# dcdc.net
KiCad netlist of a schematic drawn in Altium Designer
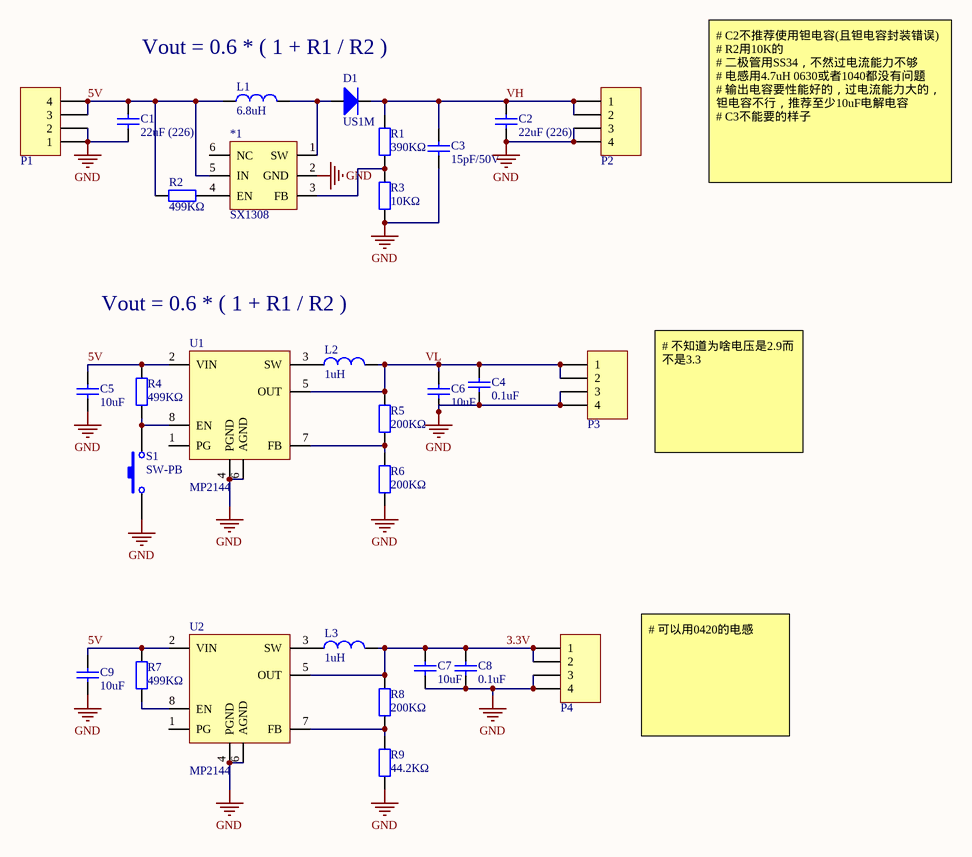
[diagram p0: dcdc.SchDoc]

(export (version "E")
  (design (tool "Eeschema 10.0.6"))
  (components
    (comp (ref "*1")
      (value "SX1308")
      (footprint "SOT23-6")
      (description "小体积高效升压电路最高28V")
      (libsource (lib "fszhang") (part "SX1308"))
    )
    (comp (ref "C1")
      (value "22uF (226)")
      (footprint "0805_C")
      (description "贴片电容")
      (libsource (lib "Miscellaneous Devices LC") (part "0805 22uF (226) 20% 25V"))
    )
    (comp (ref "C2")
      (value "22uF (226)")
      (footprint "CAP-7343")
      (description "贴片电容")
      (libsource (lib "Miscellaneous Devices LC") (part "0805 22uF (226) 20% 25V"))
    )
    (comp (ref "C3")
      (value "15pF/50V")
      (footprint "0805_C")
      (description "贴片电容")
      (libsource (lib "Miscellaneous Devices LC") (part "0805 22uF (226) 20% 25V"))
    )
    (comp (ref "C4")
      (value "0.1uF")
      (footprint "0805_C")
      (description "贴片电容")
      (libsource (lib "Miscellaneous Devices LC") (part "0805 10uF (106) 10% 25V"))
    )
    (comp (ref "C5")
      (value "10uF")
      (footprint "0805_C")
      (description "贴片电容")
      (libsource (lib "Miscellaneous Devices LC") (part "0805 10uF (106) 10% 25V"))
    )
    (comp (ref "C6")
      (value "10uF")
      (footprint "0805_C")
      (description "贴片电容")
      (libsource (lib "Miscellaneous Devices LC") (part "0805 10uF (106) 10% 25V"))
    )
    (comp (ref "C7")
      (value "10uF")
      (footprint "0805_C")
      (description "贴片电容")
      (libsource (lib "Miscellaneous Devices LC") (part "0805 10uF (106) 10% 25V"))
    )
    (comp (ref "C8")
      (value "0.1uF")
      (footprint "0805_C")
      (description "贴片电容")
      (libsource (lib "Miscellaneous Devices LC") (part "0805 10uF (106) 10% 25V"))
    )
    (comp (ref "C9")
      (value "10uF")
      (footprint "0805_C")
      (description "贴片电容")
      (libsource (lib "Miscellaneous Devices LC") (part "0805 10uF (106) 10% 25V"))
    )
    (comp (ref "D1")
      (value "US1M")
      (footprint "DIODE-SMA")
      (description "二极管")
      (fields (field (name "PUBLISHER") "Altium Limited"))
      (libsource (lib "fszhang") (part "Diode"))
    )
    (comp (ref "L1")
      (value "6.8uH")
      (footprint "CDRH104R")
      (description "电感")
      (fields (field (name "PUBLISHER") "Altium Limited"))
      (libsource (lib "fszhang") (part "Inductor"))
    )
    (comp (ref "L2")
      (value "1uH")
      (footprint "06030")
      (description "电感")
      (fields (field (name "PUBLISHER") "Altium Limited"))
      (libsource (lib "fszhang") (part "Inductor"))
    )
    (comp (ref "L3")
      (value "1uH")
      (footprint "06030")
      (description "电感")
      (fields (field (name "PUBLISHER") "Altium Limited"))
      (libsource (lib "fszhang") (part "Inductor"))
    )
    (comp (ref "P1")
      (value "Header 4")
      (footprint "HDR4X1_A")
      (description "接插件")
      (fields (field (name "PUBLISHER") "Altium Limited"))
      (libsource (lib "") (part "Header 4_1"))
    )
    (comp (ref "P2")
      (value "Header 4")
      (footprint "HDR4X1_A")
      (description "接插件")
      (fields (field (name "PUBLISHER") "Altium Limited"))
      (libsource (lib "fszhang") (part "Header 4"))
    )
    (comp (ref "P3")
      (value "Header 4")
      (footprint "HDR4X1_A")
      (description "接插件")
      (fields (field (name "PUBLISHER") "Altium Limited"))
      (libsource (lib "fszhang") (part "Header 4"))
    )
    (comp (ref "P4")
      (value "Header 4")
      (footprint "HDR4X1_A")
      (description "接插件")
      (fields (field (name "PUBLISHER") "Altium Limited"))
      (libsource (lib "fszhang") (part "Header 4"))
    )
    (comp (ref "R1")
      (value "390KΩ")
      (footprint "0805_R")
      (description "贴片电阻")
      (libsource (lib "Miscellaneous Devices LC") (part "0805 1.2KΩ (1201) 1%"))
    )
    (comp (ref "R2")
      (value "499KΩ")
      (footprint "0805_R")
      (description "贴片电阻")
      (libsource (lib "Miscellaneous Devices LC") (part "0805 100KΩ (1003) 1%"))
    )
    (comp (ref "R3")
      (value "10KΩ")
      (footprint "0805_R")
      (description "贴片电阻")
      (libsource (lib "Miscellaneous Devices LC") (part "0805 1.2KΩ (1201) 1%"))
    )
    (comp (ref "R4")
      (value "499KΩ")
      (footprint "0805_R")
      (description "贴片电阻")
      (libsource (lib "Miscellaneous Devices LC") (part "0805 200KΩ (2003) 1%"))
    )
    (comp (ref "R5")
      (value "200KΩ")
      (footprint "0805_R")
      (description "贴片电阻")
      (libsource (lib "") (part "0805 200KΩ (2003) 1%_1"))
    )
    (comp (ref "R6")
      (value "200KΩ")
      (footprint "0805_R")
      (description "贴片电阻")
      (libsource (lib "Miscellaneous Devices LC") (part "0805 200KΩ (2003) 1%"))
    )
    (comp (ref "R7")
      (value "499KΩ")
      (footprint "0805_R")
      (description "贴片电阻")
      (libsource (lib "Miscellaneous Devices LC") (part "0805 200KΩ (2003) 1%"))
    )
    (comp (ref "R8")
      (value "200KΩ")
      (footprint "0805_R")
      (description "贴片电阻")
      (libsource (lib "") (part "0805 200KΩ (2003) 1%_1"))
    )
    (comp (ref "R9")
      (value "44.2KΩ")
      (footprint "0805_R")
      (description "贴片电阻")
      (libsource (lib "Miscellaneous Devices LC") (part "0805 200KΩ (2003) 1%"))
    )
    (comp (ref "S1")
      (value "SW-PB")
      (footprint "SW_PB2_A2")
      (description "微动开关key")
      (fields (field (name "PUBLISHER") "Altium Limited"))
      (libsource (lib "fszhang") (part "SW-PB"))
    )
    (comp (ref "U1")
      (value "MP2144")
      (footprint "TSOT23-8")
      (description "小体积高效降压 有推荐pcb布局")
      (libsource (lib "fszhang") (part "MP2144"))
    )
    (comp (ref "U2")
      (value "MP2144")
      (footprint "TSOT23-8")
      (description "小体积高效降压 有推荐pcb布局")
      (libsource (lib "fszhang") (part "MP2144"))
    )
  )
  (nets
    (net (code "1") (name "/3.3V") (class "Default")
      (node (ref "C7") (pin "2") (pinfunction "2_2") (pintype "passive"))
      (node (ref "C8") (pin "2") (pinfunction "2_2") (pintype "passive"))
      (node (ref "L3") (pin "2") (pinfunction "2_2") (pintype "passive"))
      (node (ref "P4") (pin "1") (pinfunction "1_1") (pintype "passive"))
      (node (ref "P4") (pin "2") (pinfunction "2_2") (pintype "passive"))
      (node (ref "R8") (pin "1") (pinfunction "1_1") (pintype "passive"))
      (node (ref "U2") (pin "5") (pinfunction "OUT_5") (pintype "passive"))
    )
    (net (code "2") (name "/5V") (class "Default")
      (node (ref "*1") (pin "5") (pinfunction "IN_5") (pintype "passive"))
      (node (ref "C1") (pin "2") (pinfunction "2_2") (pintype "passive"))
      (node (ref "C5") (pin "2") (pinfunction "2_2") (pintype "passive"))
      (node (ref "C9") (pin "2") (pinfunction "2_2") (pintype "passive"))
      (node (ref "L1") (pin "1") (pinfunction "1_1") (pintype "passive"))
      (node (ref "P1") (pin "3") (pinfunction "3_3") (pintype "passive"))
      (node (ref "P1") (pin "4") (pinfunction "4_4") (pintype "passive"))
      (node (ref "R2") (pin "1") (pinfunction "1_1") (pintype "passive"))
      (node (ref "R4") (pin "2") (pinfunction "2_2") (pintype "passive"))
      (node (ref "R7") (pin "2") (pinfunction "2_2") (pintype "passive"))
      (node (ref "U1") (pin "2") (pinfunction "VIN_2") (pintype "passive"))
      (node (ref "U2") (pin "2") (pinfunction "VIN_2") (pintype "passive"))
    )
    (net (code "3") (name "/VH") (class "Default")
      (node (ref "C2") (pin "2") (pinfunction "2_2") (pintype "passive"))
      (node (ref "C3") (pin "2") (pinfunction "2_2") (pintype "passive"))
      (node (ref "D1") (pin "2") (pinfunction "K_2") (pintype "passive"))
      (node (ref "P2") (pin "1") (pinfunction "1_1") (pintype "passive"))
      (node (ref "P2") (pin "2") (pinfunction "2_2") (pintype "passive"))
      (node (ref "R1") (pin "2") (pinfunction "2_2") (pintype "passive"))
    )
    (net (code "4") (name "/VL") (class "Default")
      (node (ref "C4") (pin "2") (pinfunction "2_2") (pintype "passive"))
      (node (ref "C6") (pin "2") (pinfunction "2_2") (pintype "passive"))
      (node (ref "L2") (pin "2") (pinfunction "2_2") (pintype "passive"))
      (node (ref "P3") (pin "1") (pinfunction "1_1") (pintype "passive"))
      (node (ref "P3") (pin "2") (pinfunction "2_2") (pintype "passive"))
      (node (ref "R5") (pin "1") (pinfunction "1_1") (pintype "passive"))
      (node (ref "U1") (pin "5") (pinfunction "OUT_5") (pintype "passive"))
    )
    (net (code "5") (name "GND") (class "Default")
      (node (ref "*1") (pin "2") (pinfunction "GND_2") (pintype "passive"))
      (node (ref "C1") (pin "1") (pinfunction "1_1") (pintype "passive"))
      (node (ref "C2") (pin "1") (pinfunction "1_1") (pintype "passive"))
      (node (ref "C3") (pin "1") (pinfunction "1_1") (pintype "passive"))
      (node (ref "C4") (pin "1") (pinfunction "1_1") (pintype "passive"))
      (node (ref "C5") (pin "1") (pinfunction "1_1") (pintype "passive"))
      (node (ref "C6") (pin "1") (pinfunction "1_1") (pintype "passive"))
      (node (ref "C7") (pin "1") (pinfunction "1_1") (pintype "passive"))
      (node (ref "C8") (pin "1") (pinfunction "1_1") (pintype "passive"))
      (node (ref "C9") (pin "1") (pinfunction "1_1") (pintype "passive"))
      (node (ref "P1") (pin "1") (pinfunction "1_1") (pintype "passive"))
      (node (ref "P1") (pin "2") (pinfunction "2_2") (pintype "passive"))
      (node (ref "P2") (pin "3") (pinfunction "3_3") (pintype "passive"))
      (node (ref "P2") (pin "4") (pinfunction "4_4") (pintype "passive"))
      (node (ref "P3") (pin "3") (pinfunction "3_3") (pintype "passive"))
      (node (ref "P3") (pin "4") (pinfunction "4_4") (pintype "passive"))
      (node (ref "P4") (pin "3") (pinfunction "3_3") (pintype "passive"))
      (node (ref "P4") (pin "4") (pinfunction "4_4") (pintype "passive"))
      (node (ref "R3") (pin "1") (pinfunction "1_1") (pintype "passive"))
      (node (ref "R6") (pin "1") (pinfunction "1_1") (pintype "passive"))
      (node (ref "R9") (pin "1") (pinfunction "1_1") (pintype "passive"))
      (node (ref "S1") (pin "1") (pinfunction "1_1") (pintype "passive"))
      (node (ref "U1") (pin "4") (pinfunction "PGND_4") (pintype "passive"))
      (node (ref "U1") (pin "6") (pinfunction "AGND_6") (pintype "passive"))
      (node (ref "U2") (pin "4") (pinfunction "PGND_4") (pintype "passive"))
      (node (ref "U2") (pin "6") (pinfunction "AGND_6") (pintype "passive"))
    )
    (net (code "6") (name "Net-(*1-EN)") (class "Default")
      (node (ref "*1") (pin "4") (pinfunction "EN_4") (pintype "passive"))
      (node (ref "R2") (pin "2") (pinfunction "2_2") (pintype "passive"))
    )
    (net (code "7") (name "Net-(*1-FB)") (class "Default")
      (node (ref "*1") (pin "3") (pinfunction "FB_3") (pintype "passive"))
      (node (ref "R1") (pin "1") (pinfunction "1_1") (pintype "passive"))
      (node (ref "R3") (pin "2") (pinfunction "2_2") (pintype "passive"))
    )
    (net (code "8") (name "Net-(*1-SW)") (class "Default")
      (node (ref "*1") (pin "1") (pinfunction "SW_1") (pintype "passive"))
      (node (ref "D1") (pin "1") (pinfunction "A_1") (pintype "passive"))
      (node (ref "L1") (pin "2") (pinfunction "2_2") (pintype "passive"))
    )
    (net (code "9") (name "Net-(U1-EN)") (class "Default")
      (node (ref "R4") (pin "1") (pinfunction "1_1") (pintype "passive"))
      (node (ref "S1") (pin "2") (pinfunction "2_2") (pintype "passive"))
      (node (ref "U1") (pin "8") (pinfunction "EN_8") (pintype "passive"))
    )
    (net (code "10") (name "Net-(U1-FB)") (class "Default")
      (node (ref "R5") (pin "2") (pinfunction "2_2") (pintype "passive"))
      (node (ref "R6") (pin "2") (pinfunction "2_2") (pintype "passive"))
      (node (ref "U1") (pin "7") (pinfunction "FB_7") (pintype "passive"))
    )
    (net (code "11") (name "Net-(U1-SW)") (class "Default")
      (node (ref "L2") (pin "1") (pinfunction "1_1") (pintype "passive"))
      (node (ref "U1") (pin "3") (pinfunction "SW_3") (pintype "passive"))
    )
    (net (code "12") (name "Net-(U2-EN)") (class "Default")
      (node (ref "R7") (pin "1") (pinfunction "1_1") (pintype "passive"))
      (node (ref "U2") (pin "8") (pinfunction "EN_8") (pintype "passive"))
    )
    (net (code "13") (name "Net-(U2-FB)") (class "Default")
      (node (ref "R8") (pin "2") (pinfunction "2_2") (pintype "passive"))
      (node (ref "R9") (pin "2") (pinfunction "2_2") (pintype "passive"))
      (node (ref "U2") (pin "7") (pinfunction "FB_7") (pintype "passive"))
    )
    (net (code "14") (name "Net-(U2-SW)") (class "Default")
      (node (ref "L3") (pin "1") (pinfunction "1_1") (pintype "passive"))
      (node (ref "U2") (pin "3") (pinfunction "SW_3") (pintype "passive"))
    )
    (net (code "15") (name "unconnected-(*1-NC-Pad6)") (class "Default")
      (node (ref "*1") (pin "6") (pinfunction "NC_6") (pintype "passive"))
    )
    (net (code "16") (name "unconnected-(U1-PG-Pad1)") (class "Default")
      (node (ref "U1") (pin "1") (pinfunction "PG_1") (pintype "passive"))
    )
    (net (code "17") (name "unconnected-(U2-PG-Pad1)") (class "Default")
      (node (ref "U2") (pin "1") (pinfunction "PG_1") (pintype "passive"))
    )
  )
)
